# ctrlr_board.net
KiCad netlist of a schematic drawn in EAGLE
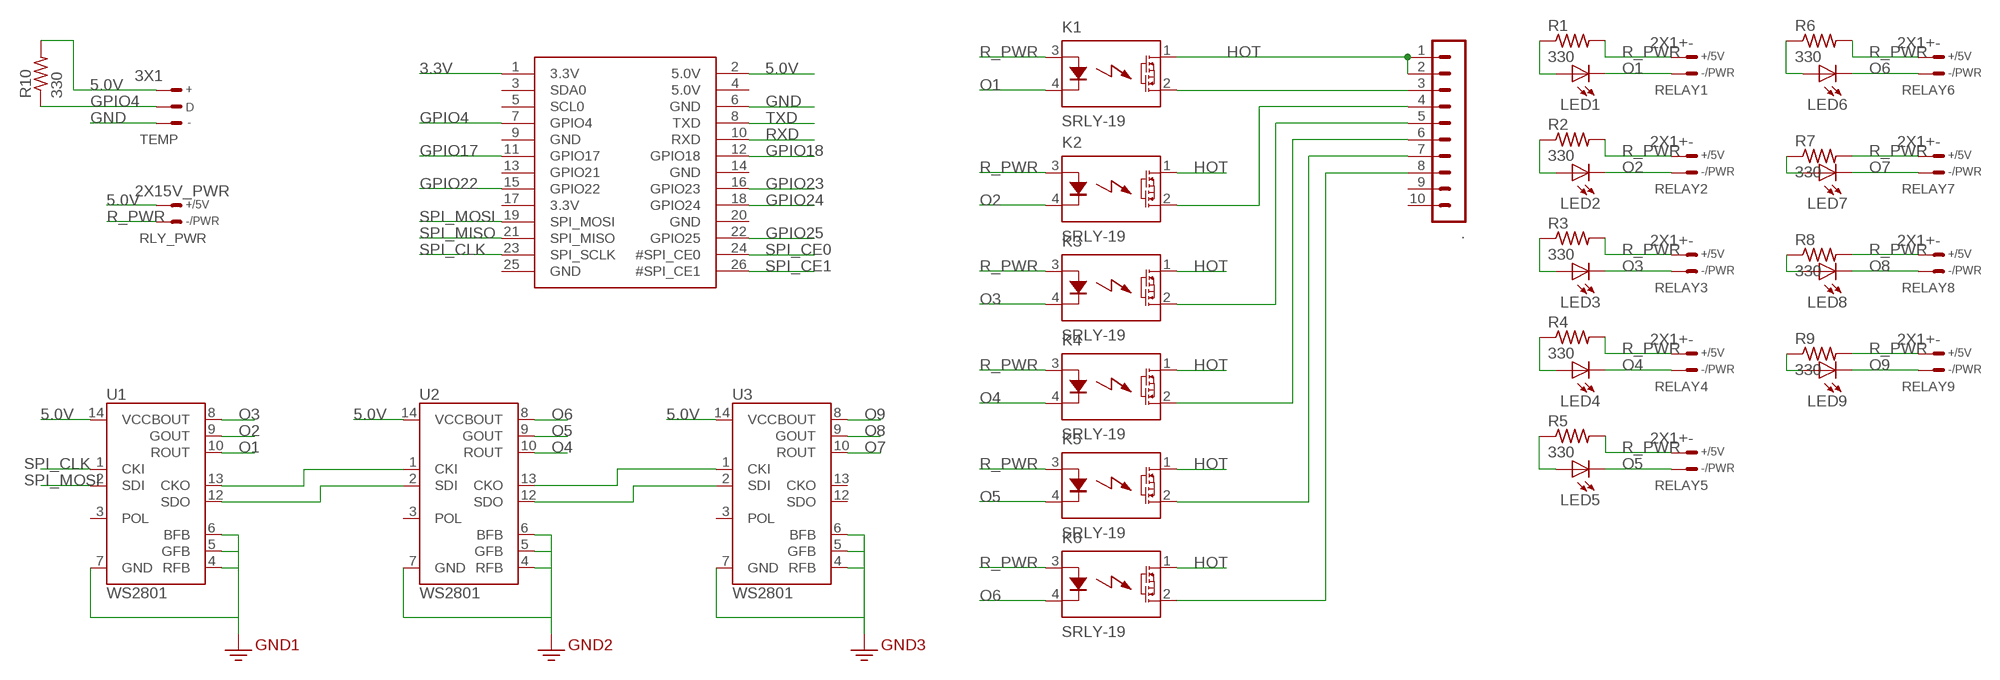
[diagram p0: schematic, sheet 1]

(export (version "E")
  (design (tool "Eeschema 10.0.6"))
  (components
    (comp (ref ".")
      (value "10X1")
      (footprint "eagle-import:HDR10")
      (libsource (lib "eagle-import") (part "10X1"))
    )
    (comp (ref "K1")
      (value "SRLY-19")
      (footprint "eagle-import:OAC5")
      (libsource (lib "eagle-import") (part "SRLY-19"))
    )
    (comp (ref "K2")
      (value "SRLY-19")
      (footprint "eagle-import:OAC5")
      (libsource (lib "eagle-import") (part "SRLY-19"))
    )
    (comp (ref "K3")
      (value "SRLY-19")
      (footprint "eagle-import:OAC5")
      (libsource (lib "eagle-import") (part "SRLY-19"))
    )
    (comp (ref "K4")
      (value "SRLY-19")
      (footprint "eagle-import:OAC5")
      (libsource (lib "eagle-import") (part "SRLY-19"))
    )
    (comp (ref "K5")
      (value "SRLY-19")
      (footprint "eagle-import:OAC5")
      (libsource (lib "eagle-import") (part "SRLY-19"))
    )
    (comp (ref "K6")
      (value "SRLY-19")
      (footprint "eagle-import:OAC5")
      (libsource (lib "eagle-import") (part "SRLY-19"))
    )
    (comp (ref "LED1")
      (value "LED")
      (footprint "eagle-import:LED0603")
      (libsource (lib "eagle-import") (part "LED"))
    )
    (comp (ref "LED2")
      (value "LED")
      (footprint "eagle-import:LED0603")
      (libsource (lib "eagle-import") (part "LED"))
    )
    (comp (ref "LED3")
      (value "LED")
      (footprint "eagle-import:LED0603")
      (libsource (lib "eagle-import") (part "LED"))
    )
    (comp (ref "LED4")
      (value "LED")
      (footprint "eagle-import:LED0603")
      (libsource (lib "eagle-import") (part "LED"))
    )
    (comp (ref "LED5")
      (value "LED")
      (footprint "eagle-import:LED0603")
      (libsource (lib "eagle-import") (part "LED"))
    )
    (comp (ref "LED6")
      (value "LED")
      (footprint "eagle-import:LED0603")
      (libsource (lib "eagle-import") (part "LED"))
    )
    (comp (ref "LED7")
      (value "LED")
      (footprint "eagle-import:LED0603")
      (libsource (lib "eagle-import") (part "LED"))
    )
    (comp (ref "LED8")
      (value "LED")
      (footprint "eagle-import:LED0603")
      (libsource (lib "eagle-import") (part "LED"))
    )
    (comp (ref "LED9")
      (value "LED")
      (footprint "eagle-import:LED0603")
      (libsource (lib "eagle-import") (part "LED"))
    )
    (comp (ref "R1")
      (value "330")
      (footprint "eagle-import:R0603")
      (libsource (lib "eagle-import") (part "RESISTOR"))
    )
    (comp (ref "R2")
      (value "330")
      (footprint "eagle-import:R0603")
      (libsource (lib "eagle-import") (part "RESISTOR"))
    )
    (comp (ref "R3")
      (value "330")
      (footprint "eagle-import:R0603")
      (libsource (lib "eagle-import") (part "RESISTOR"))
    )
    (comp (ref "R4")
      (value "330")
      (footprint "eagle-import:R0603")
      (libsource (lib "eagle-import") (part "RESISTOR"))
    )
    (comp (ref "R5")
      (value "330")
      (footprint "eagle-import:R0603")
      (libsource (lib "eagle-import") (part "RESISTOR"))
    )
    (comp (ref "R6")
      (value "330")
      (footprint "eagle-import:R0603")
      (libsource (lib "eagle-import") (part "RESISTOR"))
    )
    (comp (ref "R7")
      (value "330")
      (footprint "eagle-import:R0603")
      (libsource (lib "eagle-import") (part "RESISTOR"))
    )
    (comp (ref "R8")
      (value "330")
      (footprint "eagle-import:R0603")
      (libsource (lib "eagle-import") (part "RESISTOR"))
    )
    (comp (ref "R9")
      (value "330")
      (footprint "eagle-import:R0603")
      (libsource (lib "eagle-import") (part "RESISTOR"))
    )
    (comp (ref "R10")
      (value "330")
      (footprint "eagle-import:R0603")
      (libsource (lib "eagle-import") (part "RESISTOR"))
    )
    (comp (ref "RELAY1")
      (value "2X1+-")
      (footprint "eagle-import:HDR2")
      (libsource (lib "eagle-import") (part "2X1+-"))
    )
    (comp (ref "RELAY2")
      (value "2X1+-")
      (footprint "eagle-import:HDR2")
      (libsource (lib "eagle-import") (part "2X1+-"))
    )
    (comp (ref "RELAY3")
      (value "2X1+-")
      (footprint "eagle-import:HDR2")
      (libsource (lib "eagle-import") (part "2X1+-"))
    )
    (comp (ref "RELAY4")
      (value "2X1+-")
      (footprint "eagle-import:HDR2")
      (libsource (lib "eagle-import") (part "2X1+-"))
    )
    (comp (ref "RELAY5")
      (value "2X1+-")
      (footprint "eagle-import:HDR2")
      (libsource (lib "eagle-import") (part "2X1+-"))
    )
    (comp (ref "RELAY6")
      (value "2X1+-")
      (footprint "eagle-import:HDR2")
      (libsource (lib "eagle-import") (part "2X1+-"))
    )
    (comp (ref "RELAY7")
      (value "2X1+-")
      (footprint "eagle-import:HDR2")
      (libsource (lib "eagle-import") (part "2X1+-"))
    )
    (comp (ref "RELAY8")
      (value "2X1+-")
      (footprint "eagle-import:HDR2")
      (libsource (lib "eagle-import") (part "2X1+-"))
    )
    (comp (ref "RELAY9")
      (value "2X1+-")
      (footprint "eagle-import:HDR2")
      (libsource (lib "eagle-import") (part "2X1+-"))
    )
    (comp (ref "RLY_PWR")
      (value "2X15V_PWR")
      (footprint "eagle-import:HDR2_5V_PWR")
      (libsource (lib "eagle-import") (part "2X15V_PWR"))
    )
    (comp (ref "RPI_HDR")
      (value "RASPBERRY_PI_HEADERRASPI_HDR")
      (footprint "eagle-import:RASPBERRY_PI_HEADER")
      (libsource (lib "eagle-import") (part "RASPBERRY_PI_HEADERRASPI_HDR"))
    )
    (comp (ref "TEMP")
      (value "3X1")
      (footprint "eagle-import:HDR3")
      (libsource (lib "eagle-import") (part "3X1"))
    )
    (comp (ref "U1")
      (value "WS2801")
      (footprint "eagle-import:SOP-14")
      (libsource (lib "eagle-import") (part "WS2801"))
    )
    (comp (ref "U2")
      (value "WS2801")
      (footprint "eagle-import:SOP-14")
      (libsource (lib "eagle-import") (part "WS2801"))
    )
    (comp (ref "U3")
      (value "WS2801")
      (footprint "eagle-import:SOP-14")
      (libsource (lib "eagle-import") (part "WS2801"))
    )
  )
  (nets
    (net (code "1") (name "/3.3V") (class "Default")
      (node (ref "RPI_HDR") (pin "1") (pinfunction "3.3V_1") (pintype "power_in"))
    )
    (net (code "2") (name "/5.0V") (class "Default")
      (node (ref "R10") (pin "2") (pinfunction "2_2") (pintype "passive"))
      (node (ref "RLY_PWR") (pin "+") (pinfunction "+_+") (pintype "passive"))
      (node (ref "RPI_HDR") (pin "2") (pinfunction "5.0V_2") (pintype "power_in"))
      (node (ref "TEMP") (pin "+") (pinfunction "+_+") (pintype "passive"))
      (node (ref "U1") (pin "14") (pinfunction "VCC_14") (pintype "bidirectional"))
      (node (ref "U2") (pin "14") (pinfunction "VCC_14") (pintype "bidirectional"))
      (node (ref "U3") (pin "14") (pinfunction "VCC_14") (pintype "bidirectional"))
    )
    (net (code "3") (name "/GPIO4") (class "Default")
      (node (ref "R10") (pin "1") (pinfunction "1_1") (pintype "passive"))
      (node (ref "RPI_HDR") (pin "7") (pinfunction "GPIO4_7") (pintype "bidirectional"))
      (node (ref "TEMP") (pin "D") (pinfunction "D_D") (pintype "passive"))
    )
    (net (code "4") (name "/GPIO17") (class "Default")
      (node (ref "RPI_HDR") (pin "11") (pinfunction "GPIO17_11") (pintype "bidirectional"))
    )
    (net (code "5") (name "/GPIO18") (class "Default")
      (node (ref "RPI_HDR") (pin "12") (pinfunction "GPIO18_12") (pintype "bidirectional"))
    )
    (net (code "6") (name "/GPIO22") (class "Default")
      (node (ref "RPI_HDR") (pin "15") (pinfunction "GPIO22_15") (pintype "bidirectional"))
    )
    (net (code "7") (name "/GPIO23") (class "Default")
      (node (ref "RPI_HDR") (pin "16") (pinfunction "GPIO23_16") (pintype "bidirectional"))
    )
    (net (code "8") (name "/GPIO24") (class "Default")
      (node (ref "RPI_HDR") (pin "18") (pinfunction "GPIO24_18") (pintype "bidirectional"))
    )
    (net (code "9") (name "/GPIO25") (class "Default")
      (node (ref "RPI_HDR") (pin "22") (pinfunction "GPIO25_22") (pintype "bidirectional"))
    )
    (net (code "10") (name "/HOT") (class "Default")
      (node (ref ".") (pin "1") (pinfunction "1_1") (pintype "passive"))
      (node (ref ".") (pin "2") (pinfunction "2_2") (pintype "passive"))
      (node (ref "K1") (pin "1") (pinfunction "D1_1") (pintype "passive"))
      (node (ref "K2") (pin "1") (pinfunction "D1_1") (pintype "passive"))
      (node (ref "K3") (pin "1") (pinfunction "D1_1") (pintype "passive"))
      (node (ref "K4") (pin "1") (pinfunction "D1_1") (pintype "passive"))
      (node (ref "K5") (pin "1") (pinfunction "D1_1") (pintype "passive"))
      (node (ref "K6") (pin "1") (pinfunction "D1_1") (pintype "passive"))
    )
    (net (code "11") (name "/O1") (class "Default")
      (node (ref "K1") (pin "4") (pinfunction "K_4") (pintype "passive"))
      (node (ref "LED1") (pin "C") (pinfunction "C_C") (pintype "passive"))
      (node (ref "RELAY1") (pin "-") (pinfunction "-_-") (pintype "passive"))
      (node (ref "U1") (pin "10") (pinfunction "ROUT_10") (pintype "bidirectional"))
    )
    (net (code "12") (name "/O2") (class "Default")
      (node (ref "K2") (pin "4") (pinfunction "K_4") (pintype "passive"))
      (node (ref "LED2") (pin "C") (pinfunction "C_C") (pintype "passive"))
      (node (ref "RELAY2") (pin "-") (pinfunction "-_-") (pintype "passive"))
      (node (ref "U1") (pin "9") (pinfunction "GOUT_9") (pintype "bidirectional"))
    )
    (net (code "13") (name "/O3") (class "Default")
      (node (ref "K3") (pin "4") (pinfunction "K_4") (pintype "passive"))
      (node (ref "LED3") (pin "C") (pinfunction "C_C") (pintype "passive"))
      (node (ref "RELAY3") (pin "-") (pinfunction "-_-") (pintype "passive"))
      (node (ref "U1") (pin "8") (pinfunction "BOUT_8") (pintype "bidirectional"))
    )
    (net (code "14") (name "/O4") (class "Default")
      (node (ref "K4") (pin "4") (pinfunction "K_4") (pintype "passive"))
      (node (ref "LED4") (pin "C") (pinfunction "C_C") (pintype "passive"))
      (node (ref "RELAY4") (pin "-") (pinfunction "-_-") (pintype "passive"))
      (node (ref "U2") (pin "10") (pinfunction "ROUT_10") (pintype "bidirectional"))
    )
    (net (code "15") (name "/O5") (class "Default")
      (node (ref "K5") (pin "4") (pinfunction "K_4") (pintype "passive"))
      (node (ref "LED5") (pin "C") (pinfunction "C_C") (pintype "passive"))
      (node (ref "RELAY5") (pin "-") (pinfunction "-_-") (pintype "passive"))
      (node (ref "U2") (pin "9") (pinfunction "GOUT_9") (pintype "bidirectional"))
    )
    (net (code "16") (name "/O6") (class "Default")
      (node (ref "K6") (pin "4") (pinfunction "K_4") (pintype "passive"))
      (node (ref "LED6") (pin "C") (pinfunction "C_C") (pintype "passive"))
      (node (ref "RELAY6") (pin "-") (pinfunction "-_-") (pintype "passive"))
      (node (ref "U2") (pin "8") (pinfunction "BOUT_8") (pintype "bidirectional"))
    )
    (net (code "17") (name "/O7") (class "Default")
      (node (ref "LED7") (pin "C") (pinfunction "C_C") (pintype "passive"))
      (node (ref "RELAY7") (pin "-") (pinfunction "-_-") (pintype "passive"))
      (node (ref "U3") (pin "10") (pinfunction "ROUT_10") (pintype "bidirectional"))
    )
    (net (code "18") (name "/O8") (class "Default")
      (node (ref "LED8") (pin "C") (pinfunction "C_C") (pintype "passive"))
      (node (ref "RELAY8") (pin "-") (pinfunction "-_-") (pintype "passive"))
      (node (ref "U3") (pin "9") (pinfunction "GOUT_9") (pintype "bidirectional"))
    )
    (net (code "19") (name "/O9") (class "Default")
      (node (ref "LED9") (pin "C") (pinfunction "C_C") (pintype "passive"))
      (node (ref "RELAY9") (pin "-") (pinfunction "-_-") (pintype "passive"))
      (node (ref "U3") (pin "8") (pinfunction "BOUT_8") (pintype "bidirectional"))
    )
    (net (code "20") (name "/RXD") (class "Default")
      (node (ref "RPI_HDR") (pin "10") (pinfunction "RXD_10") (pintype "input"))
    )
    (net (code "21") (name "/R_PWR") (class "Default")
      (node (ref "K1") (pin "3") (pinfunction "A_3") (pintype "passive"))
      (node (ref "K2") (pin "3") (pinfunction "A_3") (pintype "passive"))
      (node (ref "K3") (pin "3") (pinfunction "A_3") (pintype "passive"))
      (node (ref "K4") (pin "3") (pinfunction "A_3") (pintype "passive"))
      (node (ref "K5") (pin "3") (pinfunction "A_3") (pintype "passive"))
      (node (ref "K6") (pin "3") (pinfunction "A_3") (pintype "passive"))
      (node (ref "R1") (pin "2") (pinfunction "2_2") (pintype "passive"))
      (node (ref "R2") (pin "2") (pinfunction "2_2") (pintype "passive"))
      (node (ref "R3") (pin "2") (pinfunction "2_2") (pintype "passive"))
      (node (ref "R4") (pin "2") (pinfunction "2_2") (pintype "passive"))
      (node (ref "R5") (pin "2") (pinfunction "2_2") (pintype "passive"))
      (node (ref "R6") (pin "2") (pinfunction "2_2") (pintype "passive"))
      (node (ref "R7") (pin "2") (pinfunction "2_2") (pintype "passive"))
      (node (ref "R8") (pin "2") (pinfunction "2_2") (pintype "passive"))
      (node (ref "R9") (pin "2") (pinfunction "2_2") (pintype "passive"))
      (node (ref "RELAY1") (pin "+") (pinfunction "+_+") (pintype "passive"))
      (node (ref "RELAY2") (pin "+") (pinfunction "+_+") (pintype "passive"))
      (node (ref "RELAY3") (pin "+") (pinfunction "+_+") (pintype "passive"))
      (node (ref "RELAY4") (pin "+") (pinfunction "+_+") (pintype "passive"))
      (node (ref "RELAY5") (pin "+") (pinfunction "+_+") (pintype "passive"))
      (node (ref "RELAY6") (pin "+") (pinfunction "+_+") (pintype "passive"))
      (node (ref "RELAY7") (pin "+") (pinfunction "+_+") (pintype "passive"))
      (node (ref "RELAY8") (pin "+") (pinfunction "+_+") (pintype "passive"))
      (node (ref "RELAY9") (pin "+") (pinfunction "+_+") (pintype "passive"))
      (node (ref "RLY_PWR") (pin "-") (pinfunction "-_-") (pintype "passive"))
    )
    (net (code "22") (name "/SPI_CE0") (class "Default")
      (node (ref "RPI_HDR") (pin "24") (pinfunction "#SPI_CE0_24") (pintype "output"))
    )
    (net (code "23") (name "/SPI_CE1") (class "Default")
      (node (ref "RPI_HDR") (pin "26") (pinfunction "#SPI_CE1_26") (pintype "output"))
    )
    (net (code "24") (name "/SPI_CLK") (class "Default")
      (node (ref "RPI_HDR") (pin "23") (pinfunction "SPI_SCLK_23") (pintype "output"))
      (node (ref "U1") (pin "1") (pinfunction "CKI_1") (pintype "bidirectional"))
    )
    (net (code "25") (name "/SPI_MISO") (class "Default")
      (node (ref "RPI_HDR") (pin "21") (pinfunction "SPI_MISO_21") (pintype "input"))
    )
    (net (code "26") (name "/SPI_MOSI") (class "Default")
      (node (ref "RPI_HDR") (pin "19") (pinfunction "SPI_MOSI_19") (pintype "output"))
      (node (ref "U1") (pin "2") (pinfunction "SDI_2") (pintype "bidirectional"))
    )
    (net (code "27") (name "/TXD") (class "Default")
      (node (ref "RPI_HDR") (pin "8") (pinfunction "TXD_8") (pintype "output"))
    )
    (net (code "28") (name "GND2") (class "Default")
      (node (ref "RPI_HDR") (pin "6") (pinfunction "GND_6") (pintype "power_in"))
      (node (ref "TEMP") (pin "-") (pinfunction "-_-") (pintype "passive"))
      (node (ref "U1") (pin "4") (pinfunction "RFB_4") (pintype "bidirectional"))
      (node (ref "U1") (pin "5") (pinfunction "GFB_5") (pintype "bidirectional"))
      (node (ref "U1") (pin "6") (pinfunction "BFB_6") (pintype "bidirectional"))
      (node (ref "U1") (pin "7") (pinfunction "GND_7") (pintype "bidirectional"))
      (node (ref "U2") (pin "4") (pinfunction "RFB_4") (pintype "bidirectional"))
      (node (ref "U2") (pin "5") (pinfunction "GFB_5") (pintype "bidirectional"))
      (node (ref "U2") (pin "6") (pinfunction "BFB_6") (pintype "bidirectional"))
      (node (ref "U2") (pin "7") (pinfunction "GND_7") (pintype "bidirectional"))
      (node (ref "U3") (pin "4") (pinfunction "RFB_4") (pintype "bidirectional"))
      (node (ref "U3") (pin "5") (pinfunction "GFB_5") (pintype "bidirectional"))
      (node (ref "U3") (pin "6") (pinfunction "BFB_6") (pintype "bidirectional"))
      (node (ref "U3") (pin "7") (pinfunction "GND_7") (pintype "bidirectional"))
    )
    (net (code "29") (name "Net-(K1-D2)") (class "Default")
      (node (ref ".") (pin "3") (pinfunction "3_3") (pintype "passive"))
      (node (ref "K1") (pin "2") (pinfunction "D2_2") (pintype "passive"))
    )
    (net (code "30") (name "Net-(K2-D2)") (class "Default")
      (node (ref ".") (pin "4") (pinfunction "4_4") (pintype "passive"))
      (node (ref "K2") (pin "2") (pinfunction "D2_2") (pintype "passive"))
    )
    (net (code "31") (name "Net-(K3-D2)") (class "Default")
      (node (ref ".") (pin "5") (pinfunction "5_5") (pintype "passive"))
      (node (ref "K3") (pin "2") (pinfunction "D2_2") (pintype "passive"))
    )
    (net (code "32") (name "Net-(K4-D2)") (class "Default")
      (node (ref ".") (pin "6") (pinfunction "6_6") (pintype "passive"))
      (node (ref "K4") (pin "2") (pinfunction "D2_2") (pintype "passive"))
    )
    (net (code "33") (name "Net-(K5-D2)") (class "Default")
      (node (ref ".") (pin "7") (pinfunction "7_7") (pintype "passive"))
      (node (ref "K5") (pin "2") (pinfunction "D2_2") (pintype "passive"))
    )
    (net (code "34") (name "Net-(K6-D2)") (class "Default")
      (node (ref ".") (pin "8") (pinfunction "8_8") (pintype "passive"))
      (node (ref "K6") (pin "2") (pinfunction "D2_2") (pintype "passive"))
    )
    (net (code "35") (name "Net-(LED1-PadA)") (class "Default")
      (node (ref "LED1") (pin "A") (pinfunction "A_A") (pintype "passive"))
      (node (ref "R1") (pin "1") (pinfunction "1_1") (pintype "passive"))
    )
    (net (code "36") (name "Net-(LED2-PadA)") (class "Default")
      (node (ref "LED2") (pin "A") (pinfunction "A_A") (pintype "passive"))
      (node (ref "R2") (pin "1") (pinfunction "1_1") (pintype "passive"))
    )
    (net (code "37") (name "Net-(LED3-PadA)") (class "Default")
      (node (ref "LED3") (pin "A") (pinfunction "A_A") (pintype "passive"))
      (node (ref "R3") (pin "1") (pinfunction "1_1") (pintype "passive"))
    )
    (net (code "38") (name "Net-(LED4-PadA)") (class "Default")
      (node (ref "LED4") (pin "A") (pinfunction "A_A") (pintype "passive"))
      (node (ref "R4") (pin "1") (pinfunction "1_1") (pintype "passive"))
    )
    (net (code "39") (name "Net-(LED5-PadA)") (class "Default")
      (node (ref "LED5") (pin "A") (pinfunction "A_A") (pintype "passive"))
      (node (ref "R5") (pin "1") (pinfunction "1_1") (pintype "passive"))
    )
    (net (code "40") (name "Net-(LED6-PadA)") (class "Default")
      (node (ref "LED6") (pin "A") (pinfunction "A_A") (pintype "passive"))
      (node (ref "R6") (pin "1") (pinfunction "1_1") (pintype "passive"))
    )
    (net (code "41") (name "Net-(LED7-PadA)") (class "Default")
      (node (ref "LED7") (pin "A") (pinfunction "A_A") (pintype "passive"))
      (node (ref "R7") (pin "1") (pinfunction "1_1") (pintype "passive"))
    )
    (net (code "42") (name "Net-(LED8-PadA)") (class "Default")
      (node (ref "LED8") (pin "A") (pinfunction "A_A") (pintype "passive"))
      (node (ref "R8") (pin "1") (pinfunction "1_1") (pintype "passive"))
    )
    (net (code "43") (name "Net-(LED9-PadA)") (class "Default")
      (node (ref "LED9") (pin "A") (pinfunction "A_A") (pintype "passive"))
      (node (ref "R9") (pin "1") (pinfunction "1_1") (pintype "passive"))
    )
    (net (code "44") (name "Net-(U1-CKO)") (class "Default")
      (node (ref "U1") (pin "13") (pinfunction "CKO_13") (pintype "bidirectional"))
      (node (ref "U2") (pin "1") (pinfunction "CKI_1") (pintype "bidirectional"))
    )
    (net (code "45") (name "Net-(U1-SDO)") (class "Default")
      (node (ref "U1") (pin "12") (pinfunction "SDO_12") (pintype "bidirectional"))
      (node (ref "U2") (pin "2") (pinfunction "SDI_2") (pintype "bidirectional"))
    )
    (net (code "46") (name "Net-(U2-CKO)") (class "Default")
      (node (ref "U2") (pin "13") (pinfunction "CKO_13") (pintype "bidirectional"))
      (node (ref "U3") (pin "1") (pinfunction "CKI_1") (pintype "bidirectional"))
    )
    (net (code "47") (name "Net-(U2-SDO)") (class "Default")
      (node (ref "U2") (pin "12") (pinfunction "SDO_12") (pintype "bidirectional"))
      (node (ref "U3") (pin "2") (pinfunction "SDI_2") (pintype "bidirectional"))
    )
    (net (code "48") (name "unconnected-(.-Pad9)") (class "Default")
      (node (ref ".") (pin "9") (pinfunction "9_9") (pintype "passive"))
    )
    (net (code "49") (name "unconnected-(.-Pad10)") (class "Default")
      (node (ref ".") (pin "10") (pinfunction "10_10") (pintype "passive"))
    )
    (net (code "50") (name "unconnected-(RPI_HDR-3.3V-Pad17)") (class "Default")
      (node (ref "RPI_HDR") (pin "17") (pinfunction "3.3V_17") (pintype "no_connect"))
    )
    (net (code "51") (name "unconnected-(RPI_HDR-5.0V-Pad4)") (class "Default")
      (node (ref "RPI_HDR") (pin "4") (pinfunction "5.0V_4") (pintype "no_connect"))
    )
    (net (code "52") (name "unconnected-(RPI_HDR-GND-Pad9)") (class "Default")
      (node (ref "RPI_HDR") (pin "9") (pinfunction "GND_9") (pintype "no_connect"))
    )
    (net (code "53") (name "unconnected-(RPI_HDR-GND-Pad14)") (class "Default")
      (node (ref "RPI_HDR") (pin "14") (pinfunction "GND_14") (pintype "no_connect"))
    )
    (net (code "54") (name "unconnected-(RPI_HDR-GND-Pad20)") (class "Default")
      (node (ref "RPI_HDR") (pin "20") (pinfunction "GND_20") (pintype "no_connect"))
    )
    (net (code "55") (name "unconnected-(RPI_HDR-GND-Pad25)") (class "Default")
      (node (ref "RPI_HDR") (pin "25") (pinfunction "GND_25") (pintype "no_connect"))
    )
    (net (code "56") (name "unconnected-(RPI_HDR-GPIO21-Pad13)") (class "Default")
      (node (ref "RPI_HDR") (pin "13") (pinfunction "GPIO21_13") (pintype "bidirectional"))
    )
    (net (code "57") (name "unconnected-(RPI_HDR-SCL0-Pad5)") (class "Default")
      (node (ref "RPI_HDR") (pin "5") (pinfunction "SCL0_5") (pintype "output"))
    )
    (net (code "58") (name "unconnected-(RPI_HDR-SDA0-Pad3)") (class "Default")
      (node (ref "RPI_HDR") (pin "3") (pinfunction "SDA0_3") (pintype "bidirectional"))
    )
    (net (code "59") (name "unconnected-(U1-POL-Pad3)") (class "Default")
      (node (ref "U1") (pin "3") (pinfunction "POL_3") (pintype "bidirectional"))
    )
    (net (code "60") (name "unconnected-(U2-POL-Pad3)") (class "Default")
      (node (ref "U2") (pin "3") (pinfunction "POL_3") (pintype "bidirectional"))
    )
    (net (code "61") (name "unconnected-(U3-CKO-Pad13)") (class "Default")
      (node (ref "U3") (pin "13") (pinfunction "CKO_13") (pintype "bidirectional"))
    )
    (net (code "62") (name "unconnected-(U3-POL-Pad3)") (class "Default")
      (node (ref "U3") (pin "3") (pinfunction "POL_3") (pintype "bidirectional"))
    )
    (net (code "63") (name "unconnected-(U3-SDO-Pad12)") (class "Default")
      (node (ref "U3") (pin "12") (pinfunction "SDO_12") (pintype "bidirectional"))
    )
  )
)
